# DS_Motor.net
KiCad netlist of a schematic drawn in Altium Designer
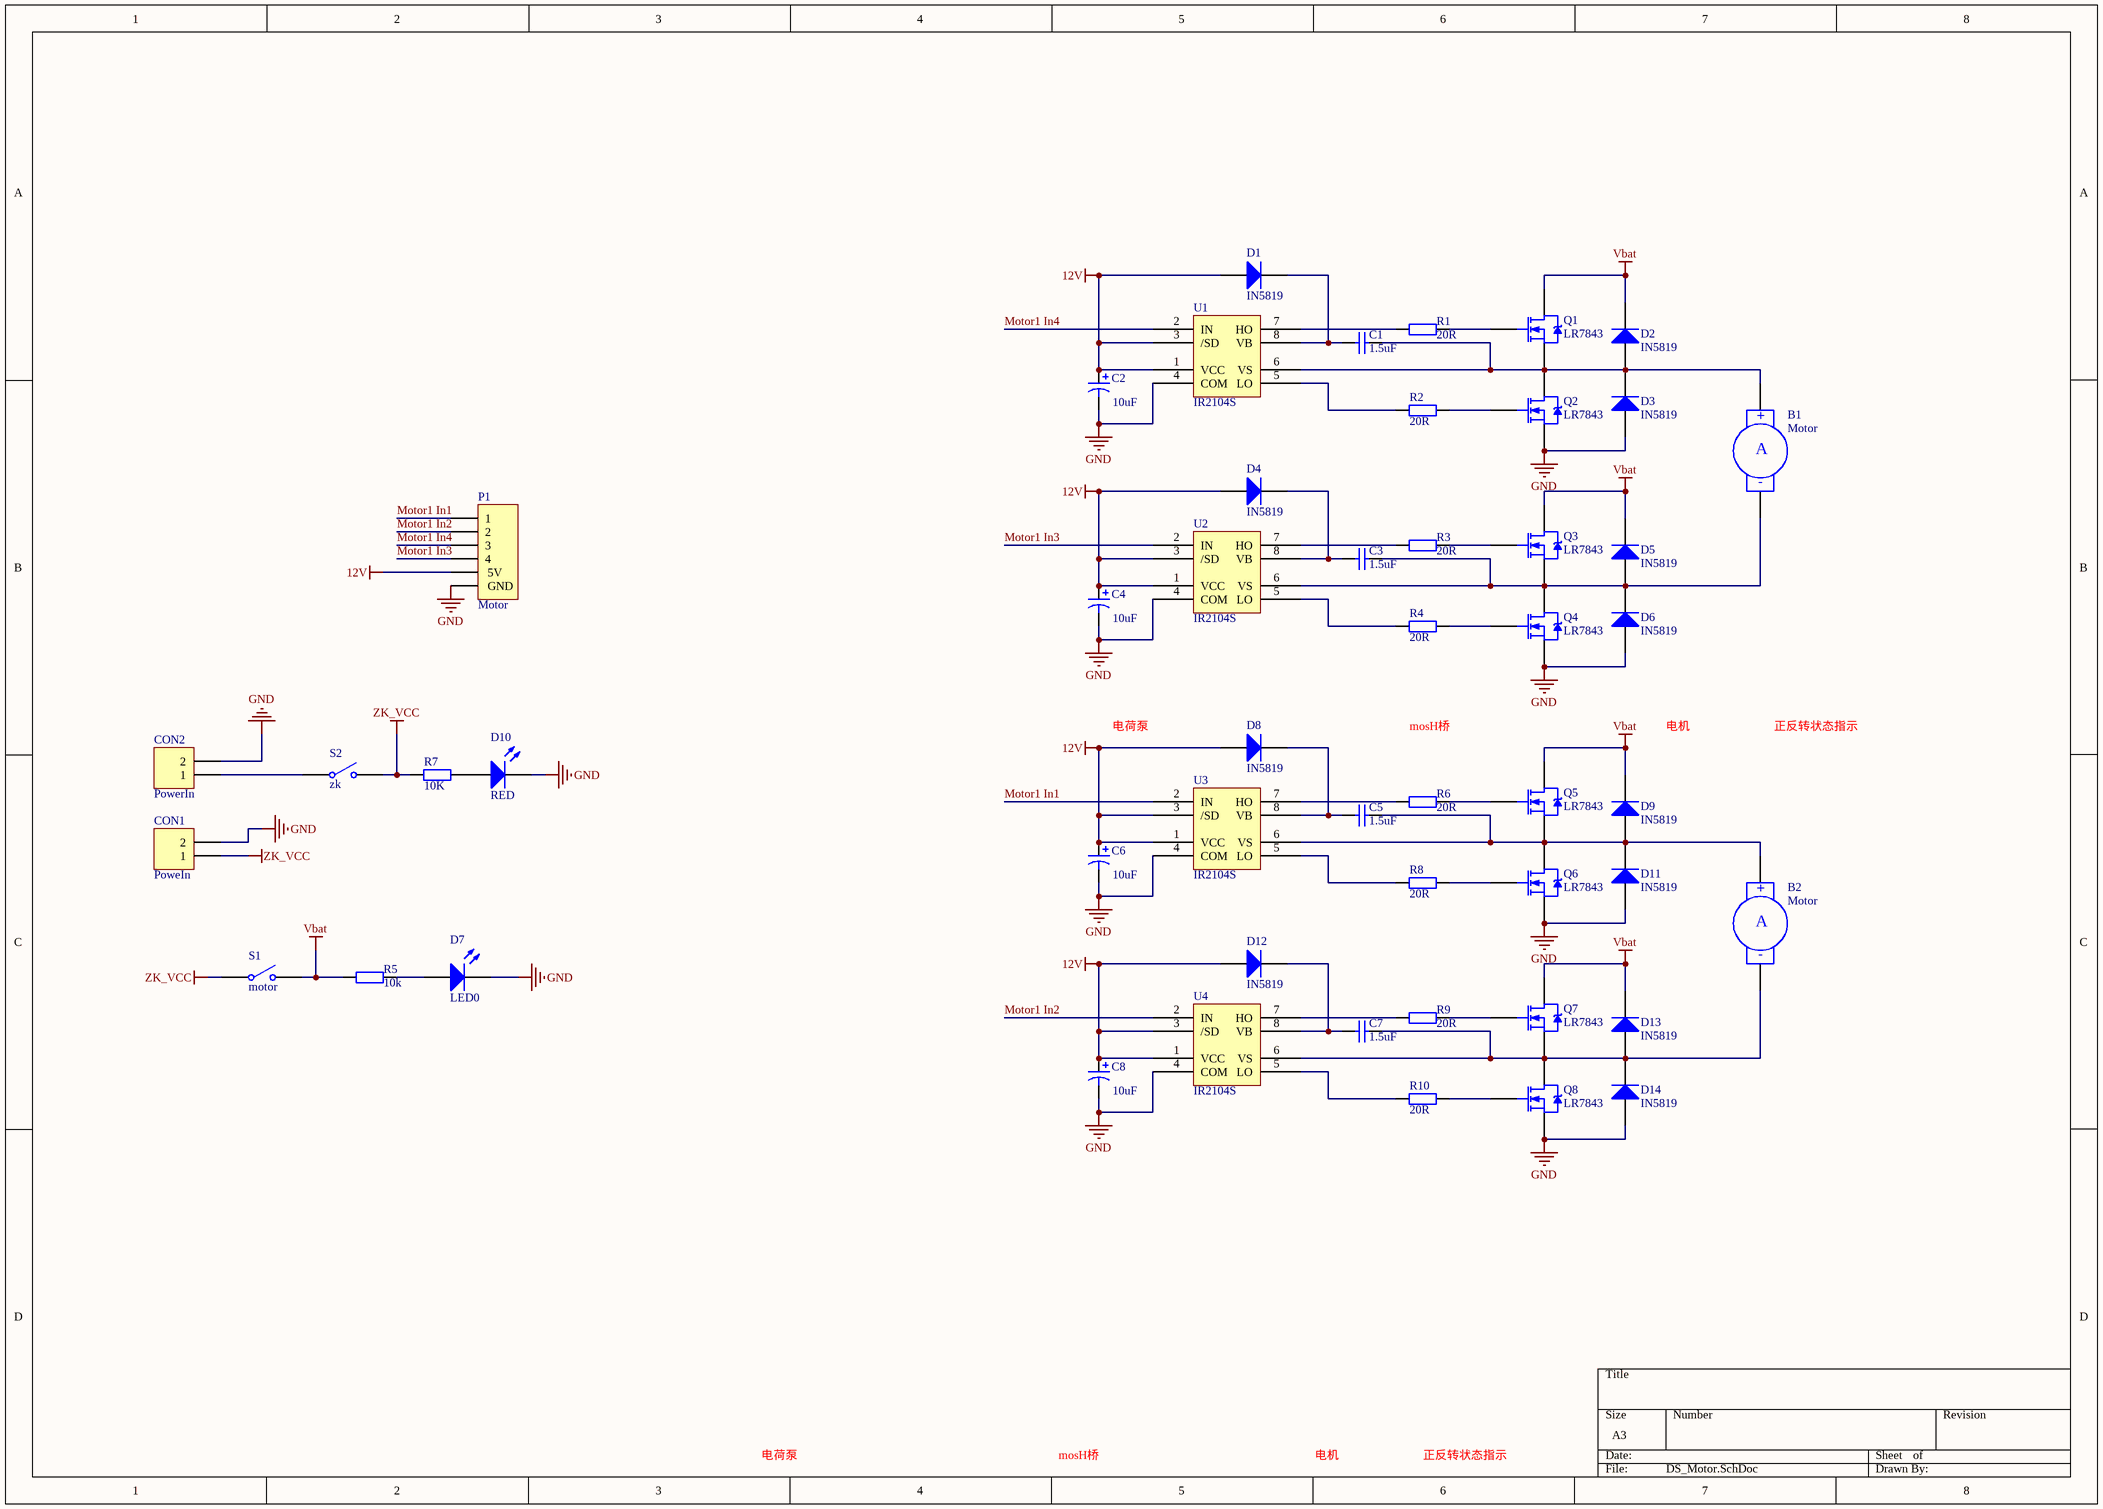
[diagram p0: DS_Motor.SchDoc]

(export (version "E")
  (design (tool "Eeschema 10.0.6"))
  (components
    (comp (ref "B1")
      (value "Motor")
      (footprint "KF301-2P")
      (description "Servo Motor")
      (fields (field (name "PUBLISHER") "Altium Limited"))
      (libsource (lib "Miscellaneous Devices") (part "Motor Servo"))
    )
    (comp (ref "B2")
      (value "Motor")
      (footprint "KF301-2P")
      (description "Servo Motor")
      (fields (field (name "PUBLISHER") "Altium Limited"))
      (libsource (lib "Miscellaneous Devices") (part "Motor Servo"))
    )
    (comp (ref "C1")
      (value "1.5uF")
      (footprint "0805")
      (description "Capacitor (Semiconductor SIM Model)")
      (fields (field (name "PUBLISHER") "Altium Limited"))
      (libsource (lib "Miscellaneous Devices") (part "Cap Semi"))
    )
    (comp (ref "C2")
      (value "10uF")
      (footprint "0805LED")
      (description "Polarized Capacitor (Surface Mount)")
      (fields (field (name "PUBLISHER") "Altium Limited"))
      (libsource (lib "Miscellaneous Devices") (part "Cap Pol3"))
    )
    (comp (ref "C3")
      (value "1.5uF")
      (footprint "0805")
      (description "Capacitor (Semiconductor SIM Model)")
      (fields (field (name "PUBLISHER") "Altium Limited"))
      (libsource (lib "Miscellaneous Devices") (part "Cap Semi"))
    )
    (comp (ref "C4")
      (value "10uF")
      (footprint "0805LED")
      (description "Polarized Capacitor (Surface Mount)")
      (fields (field (name "PUBLISHER") "Altium Limited"))
      (libsource (lib "Miscellaneous Devices") (part "Cap Pol3"))
    )
    (comp (ref "C5")
      (value "1.5uF")
      (footprint "0805")
      (description "Capacitor (Semiconductor SIM Model)")
      (fields (field (name "PUBLISHER") "Altium Limited"))
      (libsource (lib "Miscellaneous Devices") (part "Cap Semi"))
    )
    (comp (ref "C6")
      (value "10uF")
      (footprint "0805LED")
      (description "Polarized Capacitor (Surface Mount)")
      (fields (field (name "PUBLISHER") "Altium Limited"))
      (libsource (lib "Miscellaneous Devices") (part "Cap Pol3"))
    )
    (comp (ref "C7")
      (value "1.5uF")
      (footprint "0805")
      (description "Capacitor (Semiconductor SIM Model)")
      (fields (field (name "PUBLISHER") "Altium Limited"))
      (libsource (lib "Miscellaneous Devices") (part "Cap Semi"))
    )
    (comp (ref "C8")
      (value "10uF")
      (footprint "0805LED")
      (description "Polarized Capacitor (Surface Mount)")
      (fields (field (name "PUBLISHER") "Altium Limited"))
      (libsource (lib "Miscellaneous Devices") (part "Cap Pol3"))
    )
    (comp (ref "CON1")
      (value "PoweIn")
      (footprint "KF301-2P")
      (description "Header, 2-Pin")
      (fields (field (name "PUBLISHER") "Altium Limited"))
      (libsource (lib "Miscellaneous Connectors") (part "Header 2"))
    )
    (comp (ref "CON2")
      (value "PowerIn")
      (footprint "DIZUO")
      (description "Header, 2-Pin")
      (fields (field (name "PUBLISHER") "Altium Limited"))
      (libsource (lib "Miscellaneous Connectors") (part "Header 2"))
    )
    (comp (ref "D1")
      (value "IN5819")
      (footprint "0805LED")
      (description "Default Diode")
      (fields (field (name "PUBLISHER") "Altium Limited"))
      (libsource (lib "Miscellaneous Devices") (part "Diode"))
    )
    (comp (ref "D2")
      (value "IN5819")
      (footprint "0805LED")
      (description "Default Diode")
      (fields (field (name "PUBLISHER") "Altium Limited"))
      (libsource (lib "Miscellaneous Devices") (part "Diode"))
    )
    (comp (ref "D3")
      (value "IN5819")
      (footprint "0805LED")
      (description "Default Diode")
      (fields (field (name "PUBLISHER") "Altium Limited"))
      (libsource (lib "Miscellaneous Devices") (part "Diode"))
    )
    (comp (ref "D4")
      (value "IN5819")
      (footprint "0805LED")
      (description "Default Diode")
      (fields (field (name "PUBLISHER") "Altium Limited"))
      (libsource (lib "Miscellaneous Devices") (part "Diode"))
    )
    (comp (ref "D5")
      (value "IN5819")
      (footprint "0805LED")
      (description "Default Diode")
      (fields (field (name "PUBLISHER") "Altium Limited"))
      (libsource (lib "Miscellaneous Devices") (part "Diode"))
    )
    (comp (ref "D6")
      (value "IN5819")
      (footprint "0805LED")
      (description "Default Diode")
      (fields (field (name "PUBLISHER") "Altium Limited"))
      (libsource (lib "Miscellaneous Devices") (part "Diode"))
    )
    (comp (ref "D7")
      (value "LED0")
      (footprint "0805LED")
      (description "Typical INFRARED GaAs LED")
      (fields (field (name "PUBLISHER") "Altium Limited"))
      (libsource (lib "Miscellaneous Devices") (part "LED0"))
    )
    (comp (ref "D8")
      (value "IN5819")
      (footprint "0805LED")
      (description "Default Diode")
      (fields (field (name "PUBLISHER") "Altium Limited"))
      (libsource (lib "Miscellaneous Devices") (part "Diode"))
    )
    (comp (ref "D9")
      (value "IN5819")
      (footprint "0805LED")
      (description "Default Diode")
      (fields (field (name "PUBLISHER") "Altium Limited"))
      (libsource (lib "Miscellaneous Devices") (part "Diode"))
    )
    (comp (ref "D10")
      (value "RED")
      (footprint "0805LED")
      (description "Typical RED, GREEN, YELLOW, AMBER GaAs LED")
      (fields (field (name "PUBLISHER") "Altium Limited"))
      (libsource (lib "主控板原理图") (part "LED2"))
    )
    (comp (ref "D11")
      (value "IN5819")
      (footprint "0805LED")
      (description "Default Diode")
      (fields (field (name "PUBLISHER") "Altium Limited"))
      (libsource (lib "Miscellaneous Devices") (part "Diode"))
    )
    (comp (ref "D12")
      (value "IN5819")
      (footprint "0805LED")
      (description "Default Diode")
      (fields (field (name "PUBLISHER") "Altium Limited"))
      (libsource (lib "Miscellaneous Devices") (part "Diode"))
    )
    (comp (ref "D13")
      (value "IN5819")
      (footprint "0805LED")
      (description "Default Diode")
      (fields (field (name "PUBLISHER") "Altium Limited"))
      (libsource (lib "Miscellaneous Devices") (part "Diode"))
    )
    (comp (ref "D14")
      (value "IN5819")
      (footprint "0805LED")
      (description "Default Diode")
      (fields (field (name "PUBLISHER") "Altium Limited"))
      (libsource (lib "Miscellaneous Devices") (part "Diode"))
    )
    (comp (ref "P1") (value "Motor") (footprint "HDR1X6") (libsource (lib "主控板原理图") (part "Motor")))
    (comp (ref "Q1")
      (value "LR7843")
      (footprint "LR7843")
      (description "N-Channel Power MOSFET")
      (fields (field (name "PUBLISHER") "Altium Limited"))
      (libsource (lib "Miscellaneous Devices") (part "NMOS-2"))
    )
    (comp (ref "Q2")
      (value "LR7843")
      (footprint "LR7843")
      (description "N-Channel Power MOSFET")
      (fields (field (name "PUBLISHER") "Altium Limited"))
      (libsource (lib "Miscellaneous Devices") (part "NMOS-2"))
    )
    (comp (ref "Q3")
      (value "LR7843")
      (footprint "LR7843")
      (description "N-Channel Power MOSFET")
      (fields (field (name "PUBLISHER") "Altium Limited"))
      (libsource (lib "Miscellaneous Devices") (part "NMOS-2"))
    )
    (comp (ref "Q4")
      (value "LR7843")
      (footprint "LR7843")
      (description "N-Channel Power MOSFET")
      (fields (field (name "PUBLISHER") "Altium Limited"))
      (libsource (lib "Miscellaneous Devices") (part "NMOS-2"))
    )
    (comp (ref "Q5")
      (value "LR7843")
      (footprint "LR7843")
      (description "N-Channel Power MOSFET")
      (fields (field (name "PUBLISHER") "Altium Limited"))
      (libsource (lib "Miscellaneous Devices") (part "NMOS-2"))
    )
    (comp (ref "Q6")
      (value "LR7843")
      (footprint "LR7843")
      (description "N-Channel Power MOSFET")
      (fields (field (name "PUBLISHER") "Altium Limited"))
      (libsource (lib "Miscellaneous Devices") (part "NMOS-2"))
    )
    (comp (ref "Q7")
      (value "LR7843")
      (footprint "LR7843")
      (description "N-Channel Power MOSFET")
      (fields (field (name "PUBLISHER") "Altium Limited"))
      (libsource (lib "Miscellaneous Devices") (part "NMOS-2"))
    )
    (comp (ref "Q8")
      (value "LR7843")
      (footprint "LR7843")
      (description "N-Channel Power MOSFET")
      (fields (field (name "PUBLISHER") "Altium Limited"))
      (libsource (lib "Miscellaneous Devices") (part "NMOS-2"))
    )
    (comp (ref "R1")
      (value "20R")
      (footprint "0805")
      (description "Resistor")
      (fields (field (name "PUBLISHER") "Altium Limited"))
      (libsource (lib "Miscellaneous Devices") (part "Res2"))
    )
    (comp (ref "R2")
      (value "20R")
      (footprint "0805")
      (description "Resistor")
      (fields (field (name "PUBLISHER") "Altium Limited"))
      (libsource (lib "Miscellaneous Devices") (part "Res2"))
    )
    (comp (ref "R3")
      (value "20R")
      (footprint "0805")
      (description "Resistor")
      (fields (field (name "PUBLISHER") "Altium Limited"))
      (libsource (lib "Miscellaneous Devices") (part "Res2"))
    )
    (comp (ref "R4")
      (value "20R")
      (footprint "0805")
      (description "Resistor")
      (fields (field (name "PUBLISHER") "Altium Limited"))
      (libsource (lib "Miscellaneous Devices") (part "Res2"))
    )
    (comp (ref "R5")
      (value "10k")
      (footprint "0805")
      (description "Resistor")
      (fields (field (name "PUBLISHER") "Altium Limited"))
      (libsource (lib "Miscellaneous Devices") (part "Res2"))
    )
    (comp (ref "R6")
      (value "20R")
      (footprint "0805")
      (description "Resistor")
      (fields (field (name "PUBLISHER") "Altium Limited"))
      (libsource (lib "Miscellaneous Devices") (part "Res2"))
    )
    (comp (ref "R7")
      (value "10K")
      (footprint "0805")
      (description "Resistor")
      (fields (field (name "Comment") "Res2") (field (name "PUBLISHER") "Altium Limited"))
      (libsource (lib "主控板原理图") (part "Res2"))
    )
    (comp (ref "R8")
      (value "20R")
      (footprint "0805")
      (description "Resistor")
      (fields (field (name "PUBLISHER") "Altium Limited"))
      (libsource (lib "Miscellaneous Devices") (part "Res2"))
    )
    (comp (ref "R9")
      (value "20R")
      (footprint "0805")
      (description "Resistor")
      (fields (field (name "PUBLISHER") "Altium Limited"))
      (libsource (lib "Miscellaneous Devices") (part "Res2"))
    )
    (comp (ref "R10")
      (value "20R")
      (footprint "0805")
      (description "Resistor")
      (fields (field (name "PUBLISHER") "Altium Limited"))
      (libsource (lib "Miscellaneous Devices") (part "Res2"))
    )
    (comp (ref "S1")
      (value "motor")
      (footprint "SWITCH-MID")
      (description "Single-Pole, Single-Throw Switch")
      (fields (field (name "PUBLISHER") "Altium Limited"))
      (libsource (lib "Miscellaneous Devices") (part "SW-SPST"))
    )
    (comp (ref "S2")
      (value "zk")
      (footprint "SWITCH-MID")
      (description "Single-Pole, Single-Throw Switch")
      (fields (field (name "PUBLISHER") "Altium Limited"))
      (libsource (lib "Miscellaneous Devices") (part "SW-SPST"))
    )
    (comp (ref "U1") (value "IR2104S") (footprint "IR2104S") (libsource (lib "LY") (part "IR2104S")))
    (comp (ref "U2") (value "IR2104S") (footprint "IR2104S") (libsource (lib "LY") (part "IR2104S")))
    (comp (ref "U3") (value "IR2104S") (footprint "IR2104S") (libsource (lib "LY") (part "IR2104S")))
    (comp (ref "U4") (value "IR2104S") (footprint "IR2104S") (libsource (lib "LY") (part "IR2104S")))
  )
  (nets
    (net (code "1") (name "/Motor1 In1") (class "Default")
      (node (ref "P1") (pin "1") (pinfunction "1_1") (pintype "passive"))
      (node (ref "U3") (pin "2") (pinfunction "IN_2") (pintype "passive"))
    )
    (net (code "2") (name "/Motor1 In2") (class "Default")
      (node (ref "P1") (pin "2") (pinfunction "2_2") (pintype "passive"))
      (node (ref "U4") (pin "2") (pinfunction "IN_2") (pintype "passive"))
    )
    (net (code "3") (name "/Motor1 In3") (class "Default")
      (node (ref "P1") (pin "4") (pinfunction "4_4") (pintype "passive"))
      (node (ref "U2") (pin "2") (pinfunction "IN_2") (pintype "passive"))
    )
    (net (code "4") (name "/Motor1 In4") (class "Default")
      (node (ref "P1") (pin "3") (pinfunction "3_3") (pintype "passive"))
      (node (ref "U1") (pin "2") (pinfunction "IN_2") (pintype "passive"))
    )
    (net (code "5") (name "12V") (class "Default")
      (node (ref "C2") (pin "1") (pinfunction "1_1") (pintype "passive"))
      (node (ref "C4") (pin "1") (pinfunction "1_1") (pintype "passive"))
      (node (ref "C6") (pin "1") (pinfunction "1_1") (pintype "passive"))
      (node (ref "C8") (pin "1") (pinfunction "1_1") (pintype "passive"))
      (node (ref "D1") (pin "1") (pinfunction "A_1") (pintype "passive"))
      (node (ref "D12") (pin "1") (pinfunction "A_1") (pintype "passive"))
      (node (ref "D4") (pin "1") (pinfunction "A_1") (pintype "passive"))
      (node (ref "D8") (pin "1") (pinfunction "A_1") (pintype "passive"))
      (node (ref "P1") (pin "5") (pinfunction "5V_5") (pintype "passive"))
      (node (ref "U1") (pin "1") (pinfunction "VCC_1") (pintype "passive"))
      (node (ref "U1") (pin "3") (pinfunction "/SD_3") (pintype "passive"))
      (node (ref "U2") (pin "1") (pinfunction "VCC_1") (pintype "passive"))
      (node (ref "U2") (pin "3") (pinfunction "/SD_3") (pintype "passive"))
      (node (ref "U3") (pin "1") (pinfunction "VCC_1") (pintype "passive"))
      (node (ref "U3") (pin "3") (pinfunction "/SD_3") (pintype "passive"))
      (node (ref "U4") (pin "1") (pinfunction "VCC_1") (pintype "passive"))
      (node (ref "U4") (pin "3") (pinfunction "/SD_3") (pintype "passive"))
    )
    (net (code "6") (name "GND") (class "Default")
      (node (ref "C2") (pin "2") (pinfunction "2_2") (pintype "passive"))
      (node (ref "C4") (pin "2") (pinfunction "2_2") (pintype "passive"))
      (node (ref "C6") (pin "2") (pinfunction "2_2") (pintype "passive"))
      (node (ref "C8") (pin "2") (pinfunction "2_2") (pintype "passive"))
      (node (ref "CON1") (pin "2") (pinfunction "2_2") (pintype "passive"))
      (node (ref "CON2") (pin "2") (pinfunction "2_2") (pintype "passive"))
      (node (ref "D10") (pin "2") (pinfunction "K_2") (pintype "passive"))
      (node (ref "D11") (pin "1") (pinfunction "A_1") (pintype "passive"))
      (node (ref "D14") (pin "1") (pinfunction "A_1") (pintype "passive"))
      (node (ref "D3") (pin "1") (pinfunction "A_1") (pintype "passive"))
      (node (ref "D6") (pin "1") (pinfunction "A_1") (pintype "passive"))
      (node (ref "D7") (pin "2") (pinfunction "K_2") (pintype "passive"))
      (node (ref "P1") (pin "6") (pinfunction "GND_6") (pintype "passive"))
      (node (ref "Q2") (pin "3") (pinfunction "S_3") (pintype "passive"))
      (node (ref "Q4") (pin "3") (pinfunction "S_3") (pintype "passive"))
      (node (ref "Q6") (pin "3") (pinfunction "S_3") (pintype "passive"))
      (node (ref "Q8") (pin "3") (pinfunction "S_3") (pintype "passive"))
      (node (ref "U1") (pin "4") (pinfunction "COM_4") (pintype "passive"))
      (node (ref "U2") (pin "4") (pinfunction "COM_4") (pintype "passive"))
      (node (ref "U3") (pin "4") (pinfunction "COM_4") (pintype "passive"))
      (node (ref "U4") (pin "4") (pinfunction "COM_4") (pintype "passive"))
    )
    (net (code "7") (name "Net-(B1-+)") (class "Default")
      (node (ref "B1") (pin "1") (pinfunction "+_1") (pintype "passive"))
      (node (ref "C1") (pin "2") (pinfunction "2_2") (pintype "passive"))
      (node (ref "D2") (pin "1") (pinfunction "A_1") (pintype "passive"))
      (node (ref "D3") (pin "2") (pinfunction "K_2") (pintype "passive"))
      (node (ref "Q1") (pin "3") (pinfunction "S_3") (pintype "passive"))
      (node (ref "Q2") (pin "2") (pinfunction "D_2") (pintype "passive"))
      (node (ref "U1") (pin "6") (pinfunction "VS_6") (pintype "passive"))
    )
    (net (code "8") (name "Net-(B1--)") (class "Default")
      (node (ref "B1") (pin "2") (pinfunction "-_2") (pintype "passive"))
      (node (ref "C3") (pin "2") (pinfunction "2_2") (pintype "passive"))
      (node (ref "D5") (pin "1") (pinfunction "A_1") (pintype "passive"))
      (node (ref "D6") (pin "2") (pinfunction "K_2") (pintype "passive"))
      (node (ref "Q3") (pin "3") (pinfunction "S_3") (pintype "passive"))
      (node (ref "Q4") (pin "2") (pinfunction "D_2") (pintype "passive"))
      (node (ref "U2") (pin "6") (pinfunction "VS_6") (pintype "passive"))
    )
    (net (code "9") (name "Net-(B2-+)") (class "Default")
      (node (ref "B2") (pin "1") (pinfunction "+_1") (pintype "passive"))
      (node (ref "C5") (pin "2") (pinfunction "2_2") (pintype "passive"))
      (node (ref "D11") (pin "2") (pinfunction "K_2") (pintype "passive"))
      (node (ref "D9") (pin "1") (pinfunction "A_1") (pintype "passive"))
      (node (ref "Q5") (pin "3") (pinfunction "S_3") (pintype "passive"))
      (node (ref "Q6") (pin "2") (pinfunction "D_2") (pintype "passive"))
      (node (ref "U3") (pin "6") (pinfunction "VS_6") (pintype "passive"))
    )
    (net (code "10") (name "Net-(B2--)") (class "Default")
      (node (ref "B2") (pin "2") (pinfunction "-_2") (pintype "passive"))
      (node (ref "C7") (pin "2") (pinfunction "2_2") (pintype "passive"))
      (node (ref "D13") (pin "1") (pinfunction "A_1") (pintype "passive"))
      (node (ref "D14") (pin "2") (pinfunction "K_2") (pintype "passive"))
      (node (ref "Q7") (pin "3") (pinfunction "S_3") (pintype "passive"))
      (node (ref "Q8") (pin "2") (pinfunction "D_2") (pintype "passive"))
      (node (ref "U4") (pin "6") (pinfunction "VS_6") (pintype "passive"))
    )
    (net (code "11") (name "Net-(D1-K)") (class "Default")
      (node (ref "C1") (pin "1") (pinfunction "1_1") (pintype "passive"))
      (node (ref "D1") (pin "2") (pinfunction "K_2") (pintype "passive"))
      (node (ref "U1") (pin "8") (pinfunction "VB_8") (pintype "passive"))
    )
    (net (code "12") (name "Net-(D4-K)") (class "Default")
      (node (ref "C3") (pin "1") (pinfunction "1_1") (pintype "passive"))
      (node (ref "D4") (pin "2") (pinfunction "K_2") (pintype "passive"))
      (node (ref "U2") (pin "8") (pinfunction "VB_8") (pintype "passive"))
    )
    (net (code "13") (name "Net-(D7-A)") (class "Default")
      (node (ref "D7") (pin "1") (pinfunction "A_1") (pintype "passive"))
      (node (ref "R5") (pin "2") (pinfunction "2_2") (pintype "passive"))
    )
    (net (code "14") (name "Net-(D8-K)") (class "Default")
      (node (ref "C5") (pin "1") (pinfunction "1_1") (pintype "passive"))
      (node (ref "D8") (pin "2") (pinfunction "K_2") (pintype "passive"))
      (node (ref "U3") (pin "8") (pinfunction "VB_8") (pintype "passive"))
    )
    (net (code "15") (name "Net-(D10-A)") (class "Default")
      (node (ref "D10") (pin "1") (pinfunction "A_1") (pintype "passive"))
      (node (ref "R7") (pin "1") (pinfunction "1_1") (pintype "passive"))
    )
    (net (code "16") (name "Net-(D12-K)") (class "Default")
      (node (ref "C7") (pin "1") (pinfunction "1_1") (pintype "passive"))
      (node (ref "D12") (pin "2") (pinfunction "K_2") (pintype "passive"))
      (node (ref "U4") (pin "8") (pinfunction "VB_8") (pintype "passive"))
    )
    (net (code "17") (name "Net-(Q1-G)") (class "Default")
      (node (ref "Q1") (pin "1") (pinfunction "G_1") (pintype "passive"))
      (node (ref "R1") (pin "2") (pinfunction "2_2") (pintype "passive"))
    )
    (net (code "18") (name "Net-(Q2-G)") (class "Default")
      (node (ref "Q2") (pin "1") (pinfunction "G_1") (pintype "passive"))
      (node (ref "R2") (pin "2") (pinfunction "2_2") (pintype "passive"))
    )
    (net (code "19") (name "Net-(Q3-G)") (class "Default")
      (node (ref "Q3") (pin "1") (pinfunction "G_1") (pintype "passive"))
      (node (ref "R3") (pin "2") (pinfunction "2_2") (pintype "passive"))
    )
    (net (code "20") (name "Net-(Q4-G)") (class "Default")
      (node (ref "Q4") (pin "1") (pinfunction "G_1") (pintype "passive"))
      (node (ref "R4") (pin "2") (pinfunction "2_2") (pintype "passive"))
    )
    (net (code "21") (name "Net-(Q5-G)") (class "Default")
      (node (ref "Q5") (pin "1") (pinfunction "G_1") (pintype "passive"))
      (node (ref "R6") (pin "2") (pinfunction "2_2") (pintype "passive"))
    )
    (net (code "22") (name "Net-(Q6-G)") (class "Default")
      (node (ref "Q6") (pin "1") (pinfunction "G_1") (pintype "passive"))
      (node (ref "R8") (pin "2") (pinfunction "2_2") (pintype "passive"))
    )
    (net (code "23") (name "Net-(Q7-G)") (class "Default")
      (node (ref "Q7") (pin "1") (pinfunction "G_1") (pintype "passive"))
      (node (ref "R9") (pin "2") (pinfunction "2_2") (pintype "passive"))
    )
    (net (code "24") (name "Net-(Q8-G)") (class "Default")
      (node (ref "Q8") (pin "1") (pinfunction "G_1") (pintype "passive"))
      (node (ref "R10") (pin "2") (pinfunction "2_2") (pintype "passive"))
    )
    (net (code "25") (name "Net-(S2-COMMON)") (class "Default")
      (node (ref "CON2") (pin "1") (pinfunction "1_1") (pintype "passive"))
      (node (ref "S2") (pin "1") (pinfunction "COMMON_1") (pintype "passive"))
    )
    (net (code "26") (name "Net-(U1-HO)") (class "Default")
      (node (ref "R1") (pin "1") (pinfunction "1_1") (pintype "passive"))
      (node (ref "U1") (pin "7") (pinfunction "HO_7") (pintype "passive"))
    )
    (net (code "27") (name "Net-(U1-LO)") (class "Default")
      (node (ref "R2") (pin "1") (pinfunction "1_1") (pintype "passive"))
      (node (ref "U1") (pin "5") (pinfunction "LO_5") (pintype "passive"))
    )
    (net (code "28") (name "Net-(U2-HO)") (class "Default")
      (node (ref "R3") (pin "1") (pinfunction "1_1") (pintype "passive"))
      (node (ref "U2") (pin "7") (pinfunction "HO_7") (pintype "passive"))
    )
    (net (code "29") (name "Net-(U2-LO)") (class "Default")
      (node (ref "R4") (pin "1") (pinfunction "1_1") (pintype "passive"))
      (node (ref "U2") (pin "5") (pinfunction "LO_5") (pintype "passive"))
    )
    (net (code "30") (name "Net-(U3-HO)") (class "Default")
      (node (ref "R6") (pin "1") (pinfunction "1_1") (pintype "passive"))
      (node (ref "U3") (pin "7") (pinfunction "HO_7") (pintype "passive"))
    )
    (net (code "31") (name "Net-(U3-LO)") (class "Default")
      (node (ref "R8") (pin "1") (pinfunction "1_1") (pintype "passive"))
      (node (ref "U3") (pin "5") (pinfunction "LO_5") (pintype "passive"))
    )
    (net (code "32") (name "Net-(U4-HO)") (class "Default")
      (node (ref "R9") (pin "1") (pinfunction "1_1") (pintype "passive"))
      (node (ref "U4") (pin "7") (pinfunction "HO_7") (pintype "passive"))
    )
    (net (code "33") (name "Net-(U4-LO)") (class "Default")
      (node (ref "R10") (pin "1") (pinfunction "1_1") (pintype "passive"))
      (node (ref "U4") (pin "5") (pinfunction "LO_5") (pintype "passive"))
    )
    (net (code "34") (name "Vbat") (class "Default")
      (node (ref "D13") (pin "2") (pinfunction "K_2") (pintype "passive"))
      (node (ref "D2") (pin "2") (pinfunction "K_2") (pintype "passive"))
      (node (ref "D5") (pin "2") (pinfunction "K_2") (pintype "passive"))
      (node (ref "D9") (pin "2") (pinfunction "K_2") (pintype "passive"))
      (node (ref "Q1") (pin "2") (pinfunction "D_2") (pintype "passive"))
      (node (ref "Q3") (pin "2") (pinfunction "D_2") (pintype "passive"))
      (node (ref "Q5") (pin "2") (pinfunction "D_2") (pintype "passive"))
      (node (ref "Q7") (pin "2") (pinfunction "D_2") (pintype "passive"))
      (node (ref "R5") (pin "1") (pinfunction "1_1") (pintype "passive"))
      (node (ref "S1") (pin "2") (pinfunction "NO_2") (pintype "passive"))
    )
    (net (code "35") (name "ZK_VCC") (class "Default")
      (node (ref "CON1") (pin "1") (pinfunction "1_1") (pintype "passive"))
      (node (ref "R7") (pin "2") (pinfunction "2_2") (pintype "passive"))
      (node (ref "S1") (pin "1") (pinfunction "COMMON_1") (pintype "passive"))
      (node (ref "S2") (pin "2") (pinfunction "NO_2") (pintype "passive"))
    )
  )
)
